# RS485_Breakout.net
KiCad netlist of a schematic drawn in EAGLE
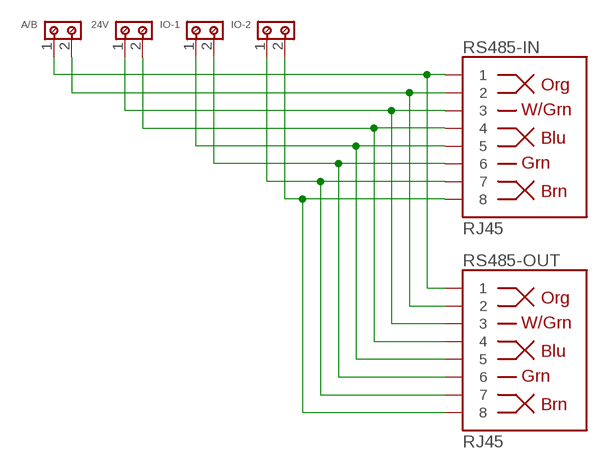
[diagram p0: schematic, sheet 1]

(export (version "E")
  (design (tool "Eeschema 10.0.6"))
  (components
    (comp (ref "24V")
      (value "691201520002")
      (footprint "eagle-import:691201520002")
      (libsource (lib "eagle-import") (part "691201520002"))
    )
    (comp (ref "A/B")
      (value "691201520002")
      (footprint "eagle-import:691201520002")
      (libsource (lib "eagle-import") (part "691201520002"))
    )
    (comp (ref "IO-1")
      (value "691201520002")
      (footprint "eagle-import:691201520002")
      (libsource (lib "eagle-import") (part "691201520002"))
    )
    (comp (ref "IO-2")
      (value "691201520002")
      (footprint "eagle-import:691201520002")
      (libsource (lib "eagle-import") (part "691201520002"))
    )
    (comp (ref "RS485-IN")
      (value "RJ45")
      (footprint "eagle-import:RJ45-8")
      (libsource (lib "eagle-import") (part "RJ45-8"))
    )
    (comp (ref "RS485-OUT")
      (value "RJ45")
      (footprint "eagle-import:RJ45-8")
      (libsource (lib "eagle-import") (part "RJ45-8"))
    )
  )
  (nets
    (net (code "1") (name "Net-(24V-Pad1)") (class "Default")
      (node (ref "24V") (pin "1") (pinfunction "1_1") (pintype "passive"))
      (node (ref "RS485-IN") (pin "3") (pinfunction "3_3") (pintype "bidirectional"))
      (node (ref "RS485-OUT") (pin "3") (pinfunction "3_3") (pintype "bidirectional"))
    )
    (net (code "2") (name "Net-(24V-Pad2)") (class "Default")
      (node (ref "24V") (pin "2") (pinfunction "2_2") (pintype "passive"))
      (node (ref "RS485-IN") (pin "4") (pinfunction "4_4") (pintype "bidirectional"))
      (node (ref "RS485-OUT") (pin "4") (pinfunction "4_4") (pintype "bidirectional"))
    )
    (net (code "3") (name "Net-(A/B-Pad1)") (class "Default")
      (node (ref "A/B") (pin "1") (pinfunction "1_1") (pintype "passive"))
      (node (ref "RS485-IN") (pin "1") (pinfunction "1_1") (pintype "bidirectional"))
      (node (ref "RS485-OUT") (pin "1") (pinfunction "1_1") (pintype "bidirectional"))
    )
    (net (code "4") (name "Net-(A/B-Pad2)") (class "Default")
      (node (ref "A/B") (pin "2") (pinfunction "2_2") (pintype "passive"))
      (node (ref "RS485-IN") (pin "2") (pinfunction "2_2") (pintype "bidirectional"))
      (node (ref "RS485-OUT") (pin "2") (pinfunction "2_2") (pintype "bidirectional"))
    )
    (net (code "5") (name "Net-(IO-1-Pad1)") (class "Default")
      (node (ref "IO-1") (pin "1") (pinfunction "1_1") (pintype "passive"))
      (node (ref "RS485-IN") (pin "5") (pinfunction "5_5") (pintype "bidirectional"))
      (node (ref "RS485-OUT") (pin "5") (pinfunction "5_5") (pintype "bidirectional"))
    )
    (net (code "6") (name "Net-(IO-1-Pad2)") (class "Default")
      (node (ref "IO-1") (pin "2") (pinfunction "2_2") (pintype "passive"))
      (node (ref "RS485-IN") (pin "6") (pinfunction "6_6") (pintype "bidirectional"))
      (node (ref "RS485-OUT") (pin "6") (pinfunction "6_6") (pintype "bidirectional"))
    )
    (net (code "7") (name "Net-(IO-2-Pad1)") (class "Default")
      (node (ref "IO-2") (pin "1") (pinfunction "1_1") (pintype "passive"))
      (node (ref "RS485-IN") (pin "7") (pinfunction "7_7") (pintype "bidirectional"))
      (node (ref "RS485-OUT") (pin "7") (pinfunction "7_7") (pintype "bidirectional"))
    )
    (net (code "8") (name "Net-(IO-2-Pad2)") (class "Default")
      (node (ref "IO-2") (pin "2") (pinfunction "2_2") (pintype "passive"))
      (node (ref "RS485-IN") (pin "8") (pinfunction "8_8") (pintype "bidirectional"))
      (node (ref "RS485-OUT") (pin "8") (pinfunction "8_8") (pintype "bidirectional"))
    )
  )
)
